# TEMP_SCH.net
KiCad netlist of a schematic drawn in Altium Designer
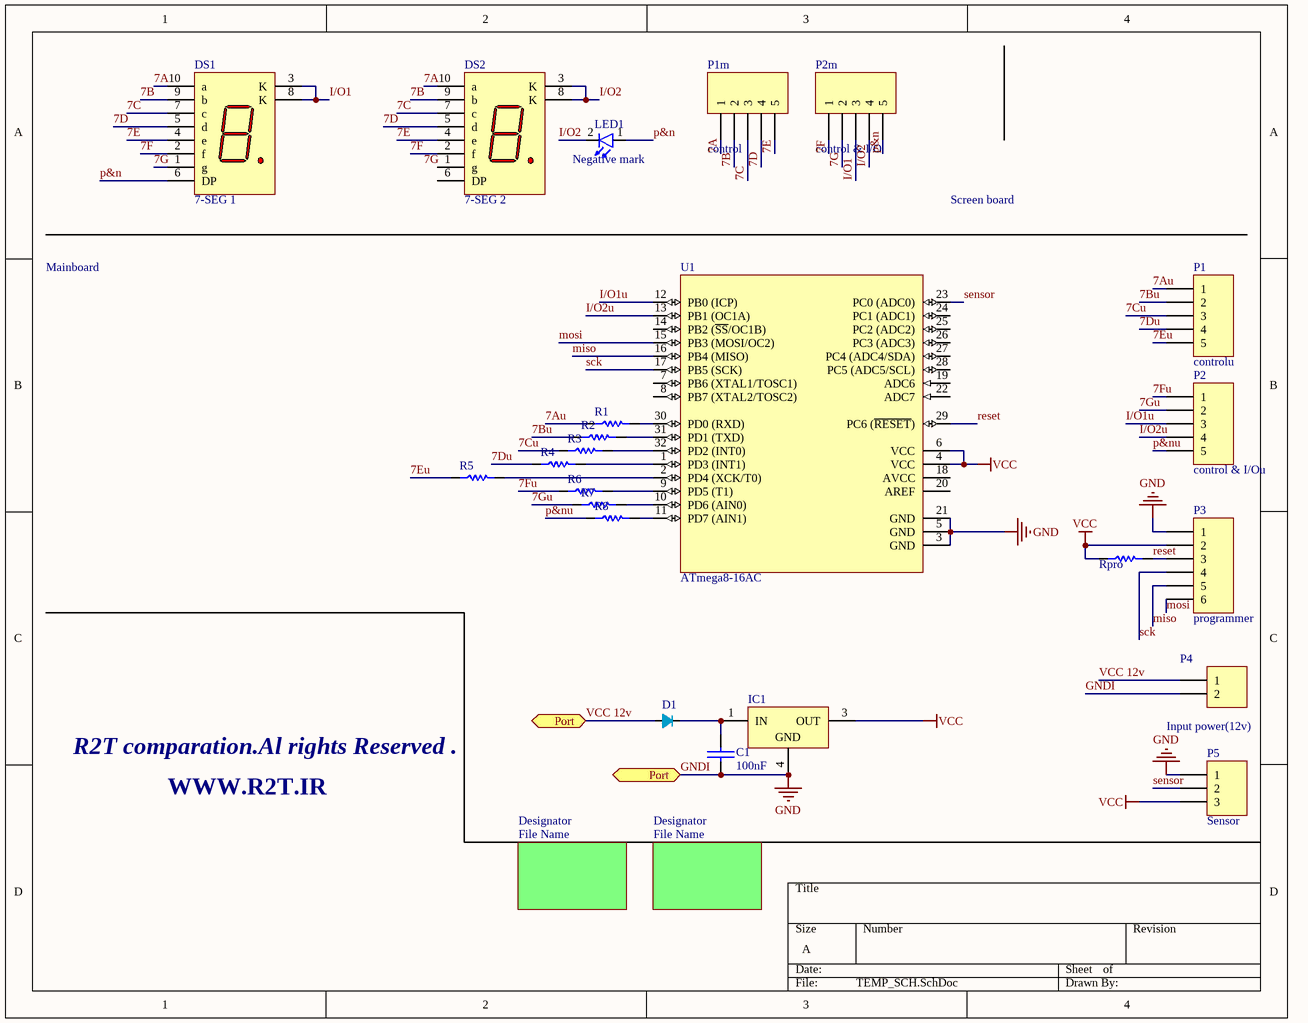
[diagram p0: TEMP_SCH.SchDoc]

(export (version "E")
  (design (tool "Eeschema 10.0.6"))
  (components
    (comp (ref "C1")
      (value "100nF")
      (footprint "SMD_CAP_1206")
      (description "Bipolar Capacitor")
      (fields (field (name "VOLTAGE") "100V") (field (name "DESIGNER") "Saeid Jorablo"))
      (libsource (lib "My Library") (part "Cap-Bipolar"))
    )
    (comp (ref "D1")
      (value "SMD Diodes")
      (footprint "DO-214AC ( SMD Diode )")
      (fields (field (name "DESIGNER :") "Hamed Jafarzadeh"))
      (libsource (lib "R2T Team Library") (part "SMD Diodes"))
    )
    (comp (ref "DS1")
      (value "7-SEG 1")
      (footprint "F-10")
      (description "10 mm Slim Font, HER 7-Segment Display: CC, RH DP")
      (fields (field (name "PUBLISHER") "Altium Limited"))
      (libsource (lib "Avago LED Display 7-Segment, 1-Digit") (part "HDSP-303E"))
    )
    (comp (ref "DS2")
      (value "7-SEG 2")
      (footprint "F-10")
      (description "10 mm Slim Font, HER 7-Segment Display: CC, RH DP")
      (fields (field (name "PUBLISHER") "Altium Limited"))
      (libsource (lib "Avago LED Display 7-Segment, 1-Digit") (part "HDSP-303E"))
    )
    (comp (ref "IC1")
      (value "L78M05")
      (footprint "TO-252")
      (description "Precision 500mA Regulator")
      (libsource (lib "My Library") (part "L78M05"))
    )
    (comp (ref "LED1")
      (value "Negative mark")
      (footprint "LED SMD 1206")
      (description "LED")
      (fields (field (name "DESIGNER") "Saeid Jorablo"))
      (libsource (lib "My Library") (part "LED"))
    )
    (comp (ref "P1")
      (value "controlu")
      (footprint "HDR1X5")
      (description "Header, 5-Pin")
      (fields (field (name "PUBLISHER") "Altium Limited"))
      (libsource (lib "") (part "Header 5_1"))
    )
    (comp (ref "P1m")
      (value "control")
      (footprint "HDR1X5")
      (description "Header, 5-Pin")
      (fields (field (name "PUBLISHER") "Altium Limited"))
      (libsource (lib "Miscellaneous Connectors") (part "Header 5"))
    )
    (comp (ref "P2")
      (value "control & I/Ou")
      (footprint "HDR1X5")
      (description "Header, 5-Pin")
      (fields (field (name "PUBLISHER") "Altium Limited"))
      (libsource (lib "") (part "Header 5_1"))
    )
    (comp (ref "P2m")
      (value "control & I/O")
      (footprint "HDR1X5")
      (description "Header, 5-Pin")
      (fields (field (name "PUBLISHER") "Altium Limited"))
      (libsource (lib "Miscellaneous Connectors") (part "Header 5"))
    )
    (comp (ref "P3")
      (value "programmer")
      (footprint "HDR1X6")
      (description "Header, 6-Pin")
      (fields (field (name "PUBLISHER") "Altium Limited"))
      (libsource (lib "Miscellaneous Connectors") (part "Header 6"))
    )
    (comp (ref "P4")
      (value "Input power(12v)")
      (footprint "HDR1X2")
      (description "Header, 2-Pin")
      (fields (field (name "PUBLISHER") "Altium Limited"))
      (libsource (lib "Miscellaneous Connectors") (part "Header 2"))
    )
    (comp (ref "P5")
      (value "Sensor")
      (footprint "HDR1X3")
      (description "Header, 3-Pin")
      (fields (field (name "PUBLISHER") "Altium Limited"))
      (libsource (lib "Miscellaneous Connectors") (part "Header 3"))
    )
    (comp (ref "R1")
      (value "330")
      (footprint "RES 0805 (2012X06L)")
      (description "Resistor")
      (fields (field (name "TOLERANCE") "5%") (field (name "POWER") "1/8 W"))
      (libsource (lib "My Library") (part "Resistor"))
    )
    (comp (ref "R2")
      (value "330")
      (footprint "RES 0805 (2012X06L)")
      (description "Resistor")
      (fields (field (name "TOLERANCE") "5%") (field (name "POWER") "1/8 W"))
      (libsource (lib "My Library") (part "Resistor"))
    )
    (comp (ref "R3")
      (value "330")
      (footprint "RES 0805 (2012X06L)")
      (description "Resistor")
      (fields (field (name "TOLERANCE") "5%") (field (name "POWER") "1/8 W"))
      (libsource (lib "My Library") (part "Resistor"))
    )
    (comp (ref "R4")
      (value "330")
      (footprint "RES 0805 (2012X06L)")
      (description "Resistor")
      (fields (field (name "TOLERANCE") "5%") (field (name "POWER") "1/8 W"))
      (libsource (lib "My Library") (part "Resistor"))
    )
    (comp (ref "R5")
      (value "330")
      (footprint "RES 0805 (2012X06L)")
      (description "Resistor")
      (fields (field (name "TOLERANCE") "5%") (field (name "POWER") "1/8 W"))
      (libsource (lib "My Library") (part "Resistor"))
    )
    (comp (ref "R6")
      (value "330")
      (footprint "RES 0805 (2012X06L)")
      (description "Resistor")
      (fields (field (name "TOLERANCE") "5%") (field (name "POWER") "1/8 W"))
      (libsource (lib "My Library") (part "Resistor"))
    )
    (comp (ref "R7")
      (value "330")
      (footprint "RES 0805 (2012X06L)")
      (description "Resistor")
      (fields (field (name "TOLERANCE") "5%") (field (name "POWER") "1/8 W"))
      (libsource (lib "My Library") (part "Resistor"))
    )
    (comp (ref "R8")
      (value "330")
      (footprint "RES 0805 (2012X06L)")
      (description "Resistor")
      (fields (field (name "TOLERANCE") "5%") (field (name "POWER") "1/8 W"))
      (libsource (lib "My Library") (part "Resistor"))
    )
    (comp (ref "Rpro")
      (value "1K")
      (footprint "RES 0805 (2012X06L)")
      (description "Resistor")
      (fields (field (name "TOLERANCE") "5%") (field (name "POWER") "1/8 W"))
      (libsource (lib "My Library") (part "Resistor"))
    )
    (comp (ref "U1")
      (value "ATmega8-16AC")
      (footprint "32A_N")
      (description "8-Bit AVR Microcontroller with 8K Bytes of In-System Programmable Flash Memory")
      (fields (field (name "PUBLISHER") "Altium Limited"))
      (libsource (lib "Atmel Microcontroller 8-Bit AVR") (part "ATmega8-16AC"))
    )
  )
  (nets
    (net (code "1") (name "/7A") (class "Default")
      (node (ref "DS1") (pin "10") (pinfunction "a_10") (pintype "passive"))
      (node (ref "DS2") (pin "10") (pinfunction "a_10") (pintype "passive"))
      (node (ref "P1m") (pin "1") (pinfunction "1_1") (pintype "passive"))
    )
    (net (code "2") (name "/7Au") (class "Default")
      (node (ref "P1") (pin "1") (pinfunction "1_1") (pintype "passive"))
      (node (ref "R1") (pin "1") (pinfunction "1_1") (pintype "passive"))
    )
    (net (code "3") (name "/7B") (class "Default")
      (node (ref "DS1") (pin "9") (pinfunction "b_9") (pintype "passive"))
      (node (ref "DS2") (pin "9") (pinfunction "b_9") (pintype "passive"))
      (node (ref "P1m") (pin "2") (pinfunction "2_2") (pintype "passive"))
    )
    (net (code "4") (name "/7Bu") (class "Default")
      (node (ref "P1") (pin "2") (pinfunction "2_2") (pintype "passive"))
      (node (ref "R2") (pin "1") (pinfunction "1_1") (pintype "passive"))
    )
    (net (code "5") (name "/7C") (class "Default")
      (node (ref "DS1") (pin "7") (pinfunction "c_7") (pintype "passive"))
      (node (ref "DS2") (pin "7") (pinfunction "c_7") (pintype "passive"))
      (node (ref "P1m") (pin "3") (pinfunction "3_3") (pintype "passive"))
    )
    (net (code "6") (name "/7Cu") (class "Default")
      (node (ref "P1") (pin "3") (pinfunction "3_3") (pintype "passive"))
      (node (ref "R3") (pin "1") (pinfunction "1_1") (pintype "passive"))
    )
    (net (code "7") (name "/7D") (class "Default")
      (node (ref "DS1") (pin "5") (pinfunction "d_5") (pintype "passive"))
      (node (ref "DS2") (pin "5") (pinfunction "d_5") (pintype "passive"))
      (node (ref "P1m") (pin "4") (pinfunction "4_4") (pintype "passive"))
    )
    (net (code "8") (name "/7Du") (class "Default")
      (node (ref "P1") (pin "4") (pinfunction "4_4") (pintype "passive"))
      (node (ref "R4") (pin "1") (pinfunction "1_1") (pintype "passive"))
    )
    (net (code "9") (name "/7E") (class "Default")
      (node (ref "DS1") (pin "4") (pinfunction "e_4") (pintype "passive"))
      (node (ref "DS2") (pin "4") (pinfunction "e_4") (pintype "passive"))
      (node (ref "P1m") (pin "5") (pinfunction "5_5") (pintype "passive"))
    )
    (net (code "10") (name "/7Eu") (class "Default")
      (node (ref "P1") (pin "5") (pinfunction "5_5") (pintype "passive"))
      (node (ref "R5") (pin "1") (pinfunction "1_1") (pintype "passive"))
    )
    (net (code "11") (name "/7F") (class "Default")
      (node (ref "DS1") (pin "2") (pinfunction "f_2") (pintype "passive"))
      (node (ref "DS2") (pin "2") (pinfunction "f_2") (pintype "passive"))
      (node (ref "P2m") (pin "1") (pinfunction "1_1") (pintype "passive"))
    )
    (net (code "12") (name "/7Fu") (class "Default")
      (node (ref "P2") (pin "1") (pinfunction "1_1") (pintype "passive"))
      (node (ref "R6") (pin "1") (pinfunction "1_1") (pintype "passive"))
    )
    (net (code "13") (name "/7G") (class "Default")
      (node (ref "DS1") (pin "1") (pinfunction "g_1") (pintype "passive"))
      (node (ref "P2m") (pin "2") (pinfunction "2_2") (pintype "passive"))
    )
    (net (code "14") (name "/7Gu") (class "Default")
      (node (ref "P2") (pin "2") (pinfunction "2_2") (pintype "passive"))
      (node (ref "R7") (pin "1") (pinfunction "1_1") (pintype "passive"))
    )
    (net (code "15") (name "/I{slash}O1") (class "Default")
      (node (ref "DS1") (pin "3") (pinfunction "K_3") (pintype "passive"))
      (node (ref "DS1") (pin "8") (pinfunction "K_8") (pintype "passive"))
      (node (ref "P2m") (pin "3") (pinfunction "3_3") (pintype "passive"))
    )
    (net (code "16") (name "/I{slash}O1u") (class "Default")
      (node (ref "P2") (pin "3") (pinfunction "3_3") (pintype "passive"))
      (node (ref "U1") (pin "12") (pinfunction "PB0_(ICP)_12") (pintype "bidirectional"))
    )
    (net (code "17") (name "/I{slash}O2") (class "Default")
      (node (ref "DS2") (pin "3") (pinfunction "K_3") (pintype "passive"))
      (node (ref "DS2") (pin "8") (pinfunction "K_8") (pintype "passive"))
      (node (ref "LED1") (pin "2") (pinfunction "K_2") (pintype "passive"))
      (node (ref "P2m") (pin "4") (pinfunction "4_4") (pintype "passive"))
    )
    (net (code "18") (name "/I{slash}O2u") (class "Default")
      (node (ref "P2") (pin "4") (pinfunction "4_4") (pintype "passive"))
      (node (ref "U1") (pin "13") (pinfunction "PB1_(OC1A)_13") (pintype "bidirectional"))
    )
    (net (code "19") (name "/miso") (class "Default")
      (node (ref "P3") (pin "5") (pinfunction "5_5") (pintype "passive"))
      (node (ref "U1") (pin "16") (pinfunction "PB4_(MISO)_16") (pintype "bidirectional"))
    )
    (net (code "20") (name "/mosi") (class "Default")
      (node (ref "P3") (pin "6") (pinfunction "6_6") (pintype "passive"))
      (node (ref "U1") (pin "15") (pinfunction "PB3_(MOSI/OC2)_15") (pintype "bidirectional"))
    )
    (net (code "21") (name "/p&n") (class "Default")
      (node (ref "DS1") (pin "6") (pinfunction "DP_6") (pintype "passive"))
      (node (ref "LED1") (pin "1") (pinfunction "A_1") (pintype "passive"))
      (node (ref "P2m") (pin "5") (pinfunction "5_5") (pintype "passive"))
    )
    (net (code "22") (name "/p&nu") (class "Default")
      (node (ref "P2") (pin "5") (pinfunction "5_5") (pintype "passive"))
      (node (ref "R8") (pin "1") (pinfunction "1_1") (pintype "passive"))
    )
    (net (code "23") (name "/reset") (class "Default")
      (node (ref "P3") (pin "3") (pinfunction "3_3") (pintype "passive"))
      (node (ref "Rpro") (pin "2") (pinfunction "2_2") (pintype "passive"))
      (node (ref "U1") (pin "29") (pinfunction "PC6_(~{RESET})_29") (pintype "bidirectional"))
    )
    (net (code "24") (name "/sck") (class "Default")
      (node (ref "P3") (pin "4") (pinfunction "4_4") (pintype "passive"))
      (node (ref "U1") (pin "17") (pinfunction "PB5_(SCK)_17") (pintype "bidirectional"))
    )
    (net (code "25") (name "/sensor") (class "Default")
      (node (ref "P5") (pin "2") (pinfunction "2_2") (pintype "passive"))
      (node (ref "U1") (pin "23") (pinfunction "PC0_(ADC0)_23") (pintype "bidirectional"))
    )
    (net (code "26") (name "GND") (class "Default")
      (node (ref "C1") (pin "2") (pinfunction "-_2") (pintype "passive"))
      (node (ref "D1") (pin "0") (pintype "passive"))
      (node (ref "IC1") (pin "4") (pinfunction "GND_4") (pintype "power_in"))
      (node (ref "P3") (pin "1") (pinfunction "1_1") (pintype "passive"))
      (node (ref "P4") (pin "1") (pinfunction "1_1") (pintype "passive"))
      (node (ref "P4") (pin "2") (pinfunction "2_2") (pintype "passive"))
      (node (ref "P5") (pin "1") (pinfunction "1_1") (pintype "passive"))
      (node (ref "U1") (pin "21") (pinfunction "GND_21") (pintype "power_in"))
      (node (ref "U1") (pin "3") (pinfunction "GND_3") (pintype "power_in"))
      (node (ref "U1") (pin "5") (pinfunction "GND_5") (pintype "power_in"))
    )
    (net (code "27") (name "Net-(C1-+)") (class "Default")
      (node (ref "C1") (pin "1") (pinfunction "+_1") (pintype "passive"))
      (node (ref "D1") (pin "1") (pintype "passive"))
      (node (ref "IC1") (pin "1") (pinfunction "IN_1") (pintype "power_in"))
    )
    (net (code "28") (name "Net-(U1-PD0_(RXD))") (class "Default")
      (node (ref "R1") (pin "2") (pinfunction "2_2") (pintype "passive"))
      (node (ref "U1") (pin "30") (pinfunction "PD0_(RXD)_30") (pintype "bidirectional"))
    )
    (net (code "29") (name "Net-(U1-PD1_(TXD))") (class "Default")
      (node (ref "R2") (pin "2") (pinfunction "2_2") (pintype "passive"))
      (node (ref "U1") (pin "31") (pinfunction "PD1_(TXD)_31") (pintype "bidirectional"))
    )
    (net (code "30") (name "Net-(U1-PD2_(INT0))") (class "Default")
      (node (ref "R3") (pin "2") (pinfunction "2_2") (pintype "passive"))
      (node (ref "U1") (pin "32") (pinfunction "PD2_(INT0)_32") (pintype "bidirectional"))
    )
    (net (code "31") (name "Net-(U1-PD3_(INT1))") (class "Default")
      (node (ref "R4") (pin "2") (pinfunction "2_2") (pintype "passive"))
      (node (ref "U1") (pin "1") (pinfunction "PD3_(INT1)_1") (pintype "bidirectional"))
    )
    (net (code "32") (name "Net-(U1-PD4_(XCK{slash}T0))") (class "Default")
      (node (ref "R5") (pin "2") (pinfunction "2_2") (pintype "passive"))
      (node (ref "U1") (pin "2") (pinfunction "PD4_(XCK/T0)_2") (pintype "bidirectional"))
    )
    (net (code "33") (name "Net-(U1-PD5_(T1))") (class "Default")
      (node (ref "R6") (pin "2") (pinfunction "2_2") (pintype "passive"))
      (node (ref "U1") (pin "9") (pinfunction "PD5_(T1)_9") (pintype "bidirectional"))
    )
    (net (code "34") (name "Net-(U1-PD6_(AIN0))") (class "Default")
      (node (ref "R7") (pin "2") (pinfunction "2_2") (pintype "passive"))
      (node (ref "U1") (pin "10") (pinfunction "PD6_(AIN0)_10") (pintype "bidirectional"))
    )
    (net (code "35") (name "Net-(U1-PD7_(AIN1))") (class "Default")
      (node (ref "R8") (pin "2") (pinfunction "2_2") (pintype "passive"))
      (node (ref "U1") (pin "11") (pinfunction "PD7_(AIN1)_11") (pintype "bidirectional"))
    )
    (net (code "36") (name "VCC") (class "Default")
      (node (ref "IC1") (pin "3") (pinfunction "OUT_3") (pintype "power_in"))
      (node (ref "P3") (pin "2") (pinfunction "2_2") (pintype "passive"))
      (node (ref "P5") (pin "3") (pinfunction "3_3") (pintype "passive"))
      (node (ref "Rpro") (pin "1") (pinfunction "1_1") (pintype "passive"))
      (node (ref "U1") (pin "4") (pinfunction "VCC_4") (pintype "power_in"))
      (node (ref "U1") (pin "6") (pinfunction "VCC_6") (pintype "power_in"))
    )
    (net (code "37") (name "unconnected-(DS2-DP-Pad6)") (class "Default")
      (node (ref "DS2") (pin "6") (pinfunction "DP_6") (pintype "passive"))
    )
    (net (code "38") (name "unconnected-(DS2-g-Pad1)") (class "Default")
      (node (ref "DS2") (pin "1") (pinfunction "g_1") (pintype "passive"))
    )
    (net (code "39") (name "unconnected-(U1-ADC6-Pad19)") (class "Default")
      (node (ref "U1") (pin "19") (pinfunction "ADC6_19") (pintype "input"))
    )
    (net (code "40") (name "unconnected-(U1-ADC7-Pad22)") (class "Default")
      (node (ref "U1") (pin "22") (pinfunction "ADC7_22") (pintype "input"))
    )
    (net (code "41") (name "unconnected-(U1-AREF-Pad20)") (class "Default")
      (node (ref "U1") (pin "20") (pinfunction "AREF_20") (pintype "passive"))
    )
    (net (code "42") (name "unconnected-(U1-AVCC-Pad18)") (class "Default")
      (node (ref "U1") (pin "18") (pinfunction "AVCC_18") (pintype "power_in"))
    )
    (net (code "43") (name "unconnected-(U1-PB2_(~{SS}{slash}OC1B)-Pad14)") (class "Default")
      (node (ref "U1") (pin "14") (pinfunction "PB2_(~{SS}/OC1B)_14") (pintype "bidirectional"))
    )
    (net (code "44") (name "unconnected-(U1-PB6_(XTAL1{slash}TOSC1)-Pad7)") (class "Default")
      (node (ref "U1") (pin "7") (pinfunction "PB6_(XTAL1/TOSC1)_7") (pintype "bidirectional"))
    )
    (net (code "45") (name "unconnected-(U1-PB7_(XTAL2{slash}TOSC2)-Pad8)") (class "Default")
      (node (ref "U1") (pin "8") (pinfunction "PB7_(XTAL2/TOSC2)_8") (pintype "bidirectional"))
    )
    (net (code "46") (name "unconnected-(U1-PC1_(ADC1)-Pad24)") (class "Default")
      (node (ref "U1") (pin "24") (pinfunction "PC1_(ADC1)_24") (pintype "bidirectional"))
    )
    (net (code "47") (name "unconnected-(U1-PC2_(ADC2)-Pad25)") (class "Default")
      (node (ref "U1") (pin "25") (pinfunction "PC2_(ADC2)_25") (pintype "bidirectional"))
    )
    (net (code "48") (name "unconnected-(U1-PC3_(ADC3)-Pad26)") (class "Default")
      (node (ref "U1") (pin "26") (pinfunction "PC3_(ADC3)_26") (pintype "bidirectional"))
    )
    (net (code "49") (name "unconnected-(U1-PC4_(ADC4{slash}SDA)-Pad27)") (class "Default")
      (node (ref "U1") (pin "27") (pinfunction "PC4_(ADC4/SDA)_27") (pintype "bidirectional"))
    )
    (net (code "50") (name "unconnected-(U1-PC5_(ADC5{slash}SCL)-Pad28)") (class "Default")
      (node (ref "U1") (pin "28") (pinfunction "PC5_(ADC5/SCL)_28") (pintype "bidirectional"))
    )
  )
)
